# PWMOUT.net
KiCad netlist of a schematic drawn in Altium Designer
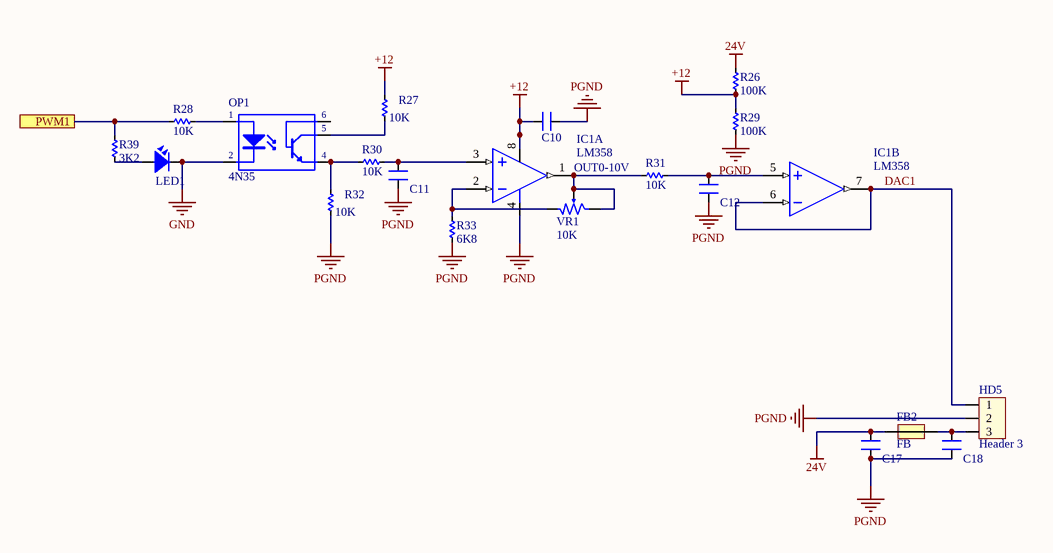
[diagram p0: PWMOUT.SchDoc]

(export (version "E")
  (design (tool "Eeschema 10.0.6"))
  (components
    (comp (ref "C10") (value "100nF") (footprint "CN-SMD-0805") (libsource (lib "nhan") (part "CN")))
    (comp (ref "C11") (value "100nF") (footprint "CN-SMD-0805") (libsource (lib "nhan") (part "CN")))
    (comp (ref "C12") (value "100nF") (footprint "CN-SMD-0805") (libsource (lib "nhan") (part "CN")))
    (comp (ref "C17") (value "CN") (footprint "CN-SMD-0805") (libsource (lib "nhan") (part "CN")))
    (comp (ref "C18") (value "CN") (footprint "CN-SMD-0805") (libsource (lib "nhan") (part "CN")))
    (comp (ref "FB2") (value "FB") (footprint "Capacitor_805") (libsource (lib "nhan") (part "FB")))
    (comp (ref "HD5")
      (value "Header 3")
      (footprint "HED3T")
      (description "Header 3 (Green)")
      (libsource (lib "syhaunguyen") (part "Hed3"))
    )
    (comp (ref "IC1")
      (value "LM358")
      (footprint "DIP8/W0.3")
      (description "Low-Power Dual Operational Amplifier")
      (libsource (lib "syhaunguyen") (part "LM358"))
    )
    (comp (ref "LED1")
      (value "LED")
      (footprint "LED-0805-Green")
      (libsource (lib "BanLinhKien") (part "LED SMD"))
    )
    (comp (ref "OP1")
      (value "4N35")
      (footprint "DIP6")
      (description "Opto")
      (libsource (lib "nhan") (part "4N35"))
    )
    (comp (ref "R26") (value "100K") (footprint "RES-SMD-0805") (libsource (lib "nhan") (part "R")))
    (comp (ref "R27") (value "10K") (footprint "RES-SMD-0805") (libsource (lib "nhan") (part "R")))
    (comp (ref "R28") (value "10K") (footprint "RES-SMD-0805") (libsource (lib "nhan") (part "R")))
    (comp (ref "R29") (value "100K") (footprint "RES-SMD-0805") (libsource (lib "nhan") (part "R")))
    (comp (ref "R30") (value "10K") (footprint "RES-SMD-0805") (libsource (lib "nhan") (part "R")))
    (comp (ref "R31") (value "10K") (footprint "RES-SMD-0805") (libsource (lib "nhan") (part "R")))
    (comp (ref "R32") (value "10K") (footprint "RES-SMD-0805") (libsource (lib "nhan") (part "R")))
    (comp (ref "R33") (value "6K8") (footprint "RES-SMD-0805") (libsource (lib "nhan") (part "R")))
    (comp (ref "R39") (value "3K2") (footprint "RES-SMD-0805") (libsource (lib "nhan") (part "R")))
    (comp (ref "VR1")
      (value "10K")
      (footprint "VR1")
      (description "Var Resistor")
      (libsource (lib "syhaunguyen") (part "VR1"))
    )
  )
  (nets
    (net (code "1") (name "+12") (class "Default")
      (node (ref "C10") (pin "2") (pinfunction "2_2") (pintype "passive"))
      (node (ref "IC1") (pin "8") (pinfunction "+V_8") (pintype "passive"))
      (node (ref "R26") (pin "1") (pinfunction "1_1") (pintype "passive"))
      (node (ref "R27") (pin "1") (pinfunction "1_1") (pintype "passive"))
      (node (ref "R29") (pin "1") (pinfunction "1_1") (pintype "passive"))
    )
    (net (code "2") (name "/DAC1") (class "Default")
      (node (ref "HD5") (pin "1") (pinfunction "1_1") (pintype "passive"))
      (node (ref "IC1") (pin "6") (pinfunction "IN-_6") (pintype "input"))
      (node (ref "IC1") (pin "7") (pinfunction "OUT_7") (pintype "output"))
    )
    (net (code "3") (name "/PWM1") (class "Default")
      (node (ref "R28") (pin "1") (pinfunction "1_1") (pintype "passive"))
      (node (ref "R39") (pin "1") (pinfunction "1_1") (pintype "passive"))
    )
    (net (code "4") (name "24V") (class "Default")
      (node (ref "C17") (pin "2") (pinfunction "2_2") (pintype "passive"))
      (node (ref "FB2") (pin "2") (pinfunction "2_2") (pintype "passive"))
      (node (ref "R26") (pin "2") (pinfunction "2_2") (pintype "passive"))
    )
    (net (code "5") (name "GND") (class "Default")
      (node (ref "LED1") (pin "2") (pinfunction "2_2") (pintype "passive"))
      (node (ref "OP1") (pin "2") (pinfunction "K_2") (pintype "passive"))
    )
    (net (code "6") (name "Net-(C18-Pad2)") (class "Default")
      (node (ref "C18") (pin "2") (pinfunction "2_2") (pintype "passive"))
      (node (ref "FB2") (pin "1") (pinfunction "1_1") (pintype "passive"))
      (node (ref "HD5") (pin "3") (pinfunction "3_3") (pintype "passive"))
    )
    (net (code "7") (name "Net-(IC1A-IN+)") (class "Default")
      (node (ref "C11") (pin "1") (pinfunction "1_1") (pintype "passive"))
      (node (ref "IC1") (pin "3") (pinfunction "IN+_3") (pintype "input"))
      (node (ref "R30") (pin "2") (pinfunction "2_2") (pintype "passive"))
    )
    (net (code "8") (name "Net-(IC1A-IN-)") (class "Default")
      (node (ref "IC1") (pin "2") (pinfunction "IN-_2") (pintype "input"))
      (node (ref "R33") (pin "1") (pinfunction "1_1") (pintype "passive"))
      (node (ref "VR1") (pin "1") (pinfunction "1_1") (pintype "passive"))
    )
    (net (code "9") (name "Net-(IC1A-OUT)") (class "Default")
      (node (ref "IC1") (pin "1") (pinfunction "OUT_1") (pintype "output"))
      (node (ref "R31") (pin "1") (pinfunction "1_1") (pintype "passive"))
      (node (ref "VR1") (pin "2") (pinfunction "2_2") (pintype "passive"))
      (node (ref "VR1") (pin "3") (pinfunction "3_3") (pintype "passive"))
    )
    (net (code "10") (name "Net-(IC1B-IN+)") (class "Default")
      (node (ref "C12") (pin "1") (pinfunction "1_1") (pintype "passive"))
      (node (ref "IC1") (pin "5") (pinfunction "IN+_5") (pintype "input"))
      (node (ref "R31") (pin "2") (pinfunction "2_2") (pintype "passive"))
    )
    (net (code "11") (name "Net-(LED1-Pad1)") (class "Default")
      (node (ref "LED1") (pin "1") (pinfunction "1_1") (pintype "passive"))
      (node (ref "R39") (pin "2") (pinfunction "2_2") (pintype "passive"))
    )
    (net (code "12") (name "Net-(OP1-A)") (class "Default")
      (node (ref "OP1") (pin "1") (pinfunction "A_1") (pintype "passive"))
      (node (ref "R28") (pin "2") (pinfunction "2_2") (pintype "passive"))
    )
    (net (code "13") (name "Net-(OP1-C-Pad5)") (class "Default")
      (node (ref "OP1") (pin "5") (pinfunction "C_5") (pintype "passive"))
      (node (ref "R27") (pin "2") (pinfunction "2_2") (pintype "passive"))
    )
    (net (code "14") (name "Net-(OP1-E)") (class "Default")
      (node (ref "OP1") (pin "4") (pinfunction "E_4") (pintype "passive"))
      (node (ref "R30") (pin "1") (pinfunction "1_1") (pintype "passive"))
      (node (ref "R32") (pin "1") (pinfunction "1_1") (pintype "passive"))
    )
    (net (code "15") (name "PGND") (class "Default")
      (node (ref "C10") (pin "1") (pinfunction "1_1") (pintype "passive"))
      (node (ref "C11") (pin "2") (pinfunction "2_2") (pintype "passive"))
      (node (ref "C12") (pin "2") (pinfunction "2_2") (pintype "passive"))
      (node (ref "C17") (pin "1") (pinfunction "1_1") (pintype "passive"))
      (node (ref "C18") (pin "1") (pinfunction "1_1") (pintype "passive"))
      (node (ref "HD5") (pin "2") (pinfunction "2_2") (pintype "passive"))
      (node (ref "IC1") (pin "4") (pinfunction "-V_4") (pintype "passive"))
      (node (ref "R29") (pin "2") (pinfunction "2_2") (pintype "passive"))
      (node (ref "R32") (pin "2") (pinfunction "2_2") (pintype "passive"))
      (node (ref "R33") (pin "2") (pinfunction "2_2") (pintype "passive"))
    )
    (net (code "16") (name "unconnected-(OP1-C-Pad6)") (class "Default")
      (node (ref "OP1") (pin "6") (pinfunction "C_6") (pintype "passive"))
    )
  )
)
